# board.net
KiCad netlist of a schematic drawn in EAGLE
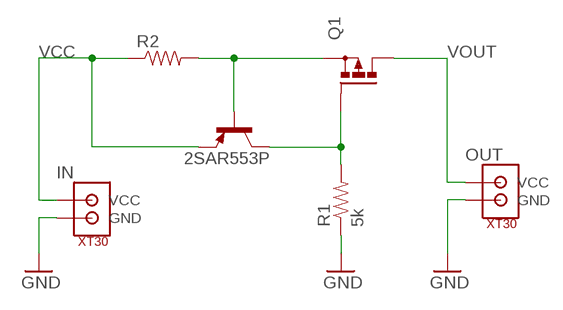
[diagram p0: schematic, sheet 1]

(export (version "E")
  (design (tool "Eeschema 10.0.6"))
  (components
    (comp (ref "2SAR553P")
      (value "-PNP-SOT89-ECB")
      (footprint "eagle-import:SOT89-ECB")
      (libsource (lib "eagle-import") (part "-PNP-SOT89-ECB"))
    )
    (comp (ref "IN")
      (value "XT30")
      (footprint "eagle-import:XT30")
      (libsource (lib "eagle-import") (part "XT30"))
    )
    (comp (ref "OUT")
      (value "XT30")
      (footprint "eagle-import:XT30")
      (libsource (lib "eagle-import") (part "XT30"))
    )
    (comp (ref "Q1")
      (value "P-MOSFET-SO8")
      (footprint "eagle-import:SO-08")
      (libsource (lib "eagle-import") (part "P-MOSFET-SO8"))
    )
    (comp (ref "R1")
      (value "5k")
      (footprint "eagle-import:1206")
      (libsource (lib "eagle-import") (part "RESISTOR1206"))
    )
    (comp (ref "R2")
      (value "RESISTOR2512")
      (footprint "eagle-import:R2512")
      (libsource (lib "eagle-import") (part "RESISTOR2512"))
    )
  )
  (nets
    (net (code "1") (name "/VCC") (class "Default")
      (node (ref "2SAR553P") (pin "E") (pinfunction "E_E") (pintype "passive"))
      (node (ref "IN") (pin "P$2") (pinfunction "VCC_P$2") (pintype "bidirectional"))
      (node (ref "R2") (pin "1") (pinfunction "1_1") (pintype "passive"))
    )
    (net (code "2") (name "/VOUT") (class "Default")
      (node (ref "OUT") (pin "P$2") (pinfunction "VCC_P$2") (pintype "bidirectional"))
      (node (ref "Q1") (pin "5") (pinfunction "D_5") (pintype "passive"))
      (node (ref "Q1") (pin "6") (pinfunction "D_6") (pintype "passive"))
      (node (ref "Q1") (pin "7") (pinfunction "D_7") (pintype "passive"))
      (node (ref "Q1") (pin "8") (pinfunction "D_8") (pintype "passive"))
    )
    (net (code "3") (name "GND") (class "Default")
      (node (ref "IN") (pin "P$1") (pinfunction "GND_P$1") (pintype "bidirectional"))
      (node (ref "OUT") (pin "P$1") (pinfunction "GND_P$1") (pintype "bidirectional"))
      (node (ref "R1") (pin "1") (pinfunction "1_1") (pintype "passive"))
    )
    (net (code "4") (name "Net-(2SAR553P-PadB)") (class "Default")
      (node (ref "2SAR553P") (pin "B") (pinfunction "B_B") (pintype "passive"))
      (node (ref "Q1") (pin "1") (pinfunction "S_1") (pintype "passive"))
      (node (ref "Q1") (pin "2") (pinfunction "S_2") (pintype "passive"))
      (node (ref "Q1") (pin "3") (pinfunction "S_3") (pintype "passive"))
      (node (ref "R2") (pin "2") (pinfunction "2_2") (pintype "passive"))
    )
    (net (code "5") (name "Net-(Q1-G)") (class "Default")
      (node (ref "2SAR553P") (pin "C") (pinfunction "C_C") (pintype "passive"))
      (node (ref "Q1") (pin "4") (pinfunction "G_4") (pintype "passive"))
      (node (ref "R1") (pin "2") (pinfunction "2_2") (pintype "passive"))
    )
  )
)
